# SYSMON.net
KiCad netlist of a schematic drawn in Altium Designer
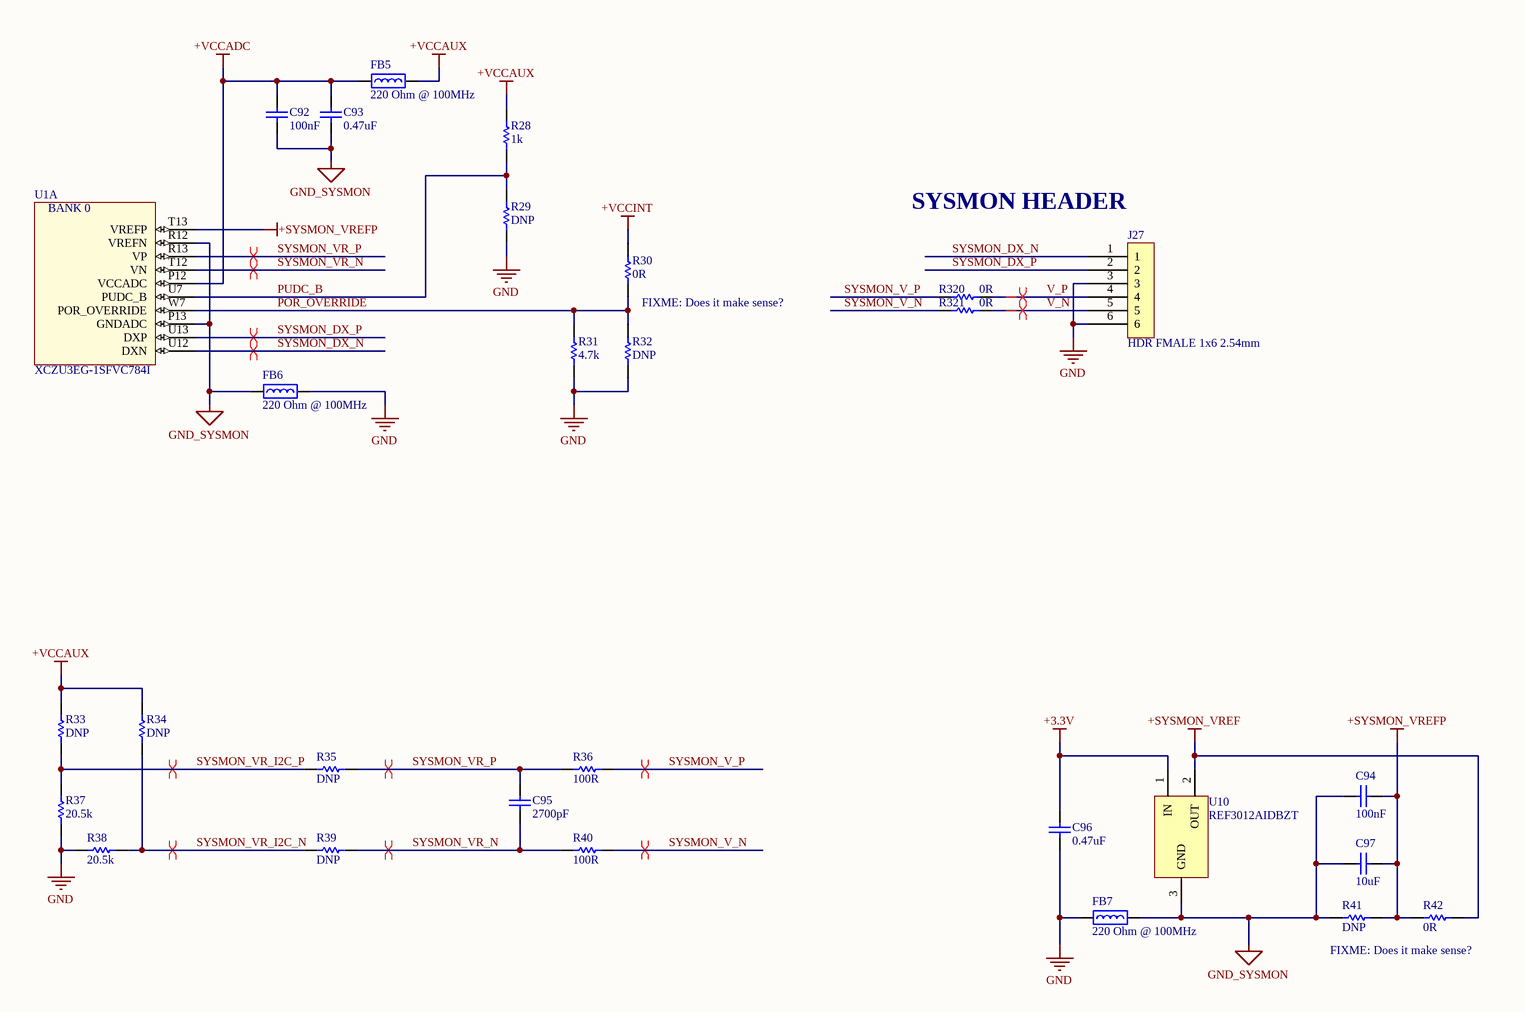
[diagram p0: SYSMON.SchDoc]

(export (version "E")
  (design (tool "Eeschema 10.0.6"))
  (components
    (comp (ref "C92")
      (value "100nF")
      (footprint "CAPC1005L_0402")
      (description "CAP CER 0.1UF 25V X7R 0402")
      (fields (field (name "VOLTAGE") "25V") (field (name "TOLERANCE") "10%"))
      (libsource (lib "Ultrascale_SchLib") (part "CAPCER0402X7R100N25V_10T"))
    )
    (comp (ref "C93")
      (value "0.47uF")
      (footprint "CAPC1005L_0402")
      (description "CAP CER 0.47UF 10V X5R 0402")
      (fields (field (name "VOLTAGE") "10V") (field (name "TOLERANCE") "10%"))
      (libsource (lib "Ultrascale_SchLib") (part "CAPCER0402X5R0U4710V_10T"))
    )
    (comp (ref "C94")
      (value "100nF")
      (footprint "CAPC1005L_0402")
      (description "CAP CER 0.1UF 25V X7R 0402")
      (fields (field (name "VOLTAGE") "25V") (field (name "TOLERANCE") "10%"))
      (libsource (lib "Ultrascale_SchLib") (part "CAPCER0402X7R100N25V_10T"))
    )
    (comp (ref "C95")
      (value "2700pF")
      (footprint "CAPC1005L_0402")
      (description "CAP CER 2700PF 50V X7R 0402")
      (fields (field (name "VOLTAGE") "50V") (field (name "TOLERANCE") "10%"))
      (libsource (lib "Ultrascale_SchLib") (part "CAPCER0402X7R2700P50V_10T"))
    )
    (comp (ref "C96")
      (value "0.47uF")
      (footprint "CAPC1005L_0402")
      (description "CAP CER 0.47UF 10V X5R 0402")
      (fields (field (name "VOLTAGE") "10V") (field (name "TOLERANCE") "10%"))
      (libsource (lib "Ultrascale_SchLib") (part "CAPCER0402X5R0U4710V_10T"))
    )
    (comp (ref "C97")
      (value "10uF")
      (footprint "CAPC1005L_0402")
      (description "CAP CER 10UF 10V X5R 0402")
      (fields (field (name "VOLTAGE") "10V") (field (name "TOLERANCE") "20%"))
      (libsource (lib "Ultrascale_SchLib") (part "CAPCER0402X5R10U10V_20T"))
    )
    (comp (ref "FB5")
      (value "BEAD0603_220_2A5_40M")
      (footprint "INDC1608N_0603")
      (description "FERRITE BEAD 220 OHM 0603 1LN")
      (fields (field (name "IMPEDANCE @ FREQUENCY") "220 Ohm @ 100MHz"))
      (libsource (lib "Ultrascale_SchLib") (part "BEAD0603_220_2A5_40M"))
    )
    (comp (ref "FB6")
      (value "BEAD0603_220_2A5_40M")
      (footprint "INDC1608N_0603")
      (description "FERRITE BEAD 220 OHM 0603 1LN")
      (fields (field (name "IMPEDANCE @ FREQUENCY") "220 Ohm @ 100MHz"))
      (libsource (lib "Ultrascale_SchLib") (part "BEAD0603_220_2A5_40M"))
    )
    (comp (ref "FB7")
      (value "BEAD0603_220_2A5_40M")
      (footprint "INDC1608N_0603")
      (description "FERRITE BEAD 220 OHM 0603 1LN")
      (fields (field (name "IMPEDANCE @ FREQUENCY") "220 Ohm @ 100MHz"))
      (libsource (lib "Ultrascale_SchLib") (part "BEAD0603_220_2A5_40M"))
    )
    (comp (ref "J27")
      (value "HDR FMALE 1x6 2.54mm")
      (footprint "Hdr_Female_1x6_2.54mm")
      (description "06-WAY SIL VERT SOCKET L/FREE")
      (fields
        (field (name ".CHECKED PCB") "MM")
        (field (name ".CHECKED SCH") "MM")
        (field (name ".CREATOR") "MM")
      )
      (libsource (lib "Ultrascale_SchLib") (part "M20-7820646"))
    )
    (comp (ref "R28")
      (value "1k")
      (footprint "RESC1005L_0402")
      (description "RES SMD 1K OHM 1% 1/10W 0402")
      (fields (field (name "POWER") "1/10W") (field (name "TOLERANCE") "1%"))
      (libsource (lib "Ultrascale_SchLib") (part "RES0402_1K_0W1_1T"))
    )
    (comp (ref "R29")
      (value "DNP")
      (footprint "RESC1005L_0402")
      (description "RES SMD 0402 Footprint")
      (fields (field (name "Comment") "RES0402"))
      (libsource (lib "Ultrascale_SchLib") (part "RES0402"))
    )
    (comp (ref "R30")
      (value "0R")
      (footprint "RESC1005L_0402")
      (description "RES SMD 0 OHM JUMPER 1/10W 0402")
      (fields (field (name "POWER") "1/10W") (field (name "Comment") "RES0402_0R_0W1"))
      (libsource (lib "Ultrascale_SchLib") (part "RES0402_0R_0W1"))
    )
    (comp (ref "R31")
      (value "4.7k")
      (footprint "RESC1005L_0402")
      (description "RES SMD 4.7K OHM 1% 1/10W 0402")
      (fields (field (name "POWER") "1/10W") (field (name "TOLERANCE") "1%"))
      (libsource (lib "Ultrascale_SchLib") (part "RES0402_4K7_0W1_1T"))
    )
    (comp (ref "R32")
      (value "DNP")
      (footprint "RESC1005L_0402")
      (description "RES SMD 0402 Footprint")
      (fields (field (name "Comment") "RES0402"))
      (libsource (lib "Ultrascale_SchLib") (part "RES0402"))
    )
    (comp (ref "R33")
      (value "DNP")
      (footprint "RESC1005L_0402")
      (description "RES SMD 0402 Footprint")
      (fields (field (name "Comment") "RES0402"))
      (libsource (lib "Ultrascale_SchLib") (part "RES0402"))
    )
    (comp (ref "R34")
      (value "DNP")
      (footprint "RESC1005L_0402")
      (description "RES SMD 0402 Footprint")
      (fields (field (name "Comment") "RES0402"))
      (libsource (lib "Ultrascale_SchLib") (part "RES0402"))
    )
    (comp (ref "R35")
      (value "DNP")
      (footprint "RESC1005L_0402")
      (description "RES SMD 0402 Footprint")
      (fields (field (name "Comment") "RES0402"))
      (libsource (lib "Ultrascale_SchLib") (part "RES0402"))
    )
    (comp (ref "R36")
      (value "100R")
      (footprint "RESC1005L_0402")
      (description "RES SMD 100 OHM 1% 1/10W 0402")
      (fields (field (name "POWER") "1/10W") (field (name "TOLERANCE") "1%"))
      (libsource (lib "Ultrascale_SchLib") (part "RES0402_100R_0W1_1T"))
    )
    (comp (ref "R37")
      (value "20.5k")
      (footprint "RESC1005L_0402")
      (description "RES SMD 20.5K OHM 1% 1/10W 0402")
      (fields (field (name "POWER") "1/10W") (field (name "TOLERANCE") "1%"))
      (libsource (lib "Ultrascale_SchLib") (part "RES0402_20K5_0W1_1T"))
    )
    (comp (ref "R38")
      (value "20.5k")
      (footprint "RESC1005L_0402")
      (description "RES SMD 20.5K OHM 1% 1/10W 0402")
      (fields (field (name "POWER") "1/10W") (field (name "TOLERANCE") "1%"))
      (libsource (lib "Ultrascale_SchLib") (part "RES0402_20K5_0W1_1T"))
    )
    (comp (ref "R39")
      (value "DNP")
      (footprint "RESC1005L_0402")
      (description "RES SMD 0402 Footprint")
      (fields (field (name "Comment") "RES0402"))
      (libsource (lib "Ultrascale_SchLib") (part "RES0402"))
    )
    (comp (ref "R40")
      (value "100R")
      (footprint "RESC1005L_0402")
      (description "RES SMD 100 OHM 1% 1/10W 0402")
      (fields (field (name "POWER") "1/10W") (field (name "TOLERANCE") "1%"))
      (libsource (lib "Ultrascale_SchLib") (part "RES0402_100R_0W1_1T"))
    )
    (comp (ref "R41")
      (value "DNP")
      (footprint "RESC1005L_0402")
      (description "RES SMD 0402 Footprint")
      (fields (field (name "Comment") "RES0402"))
      (libsource (lib "Ultrascale_SchLib") (part "RES0402"))
    )
    (comp (ref "R42")
      (value "0R")
      (footprint "RESC1005L_0402")
      (description "RES SMD 0 OHM JUMPER 1/10W 0402")
      (fields (field (name "POWER") "1/10W") (field (name "Comment") "RES0402_0R_0W1"))
      (libsource (lib "Ultrascale_SchLib") (part "RES0402_0R_0W1"))
    )
    (comp (ref "R320")
      (value "0R")
      (footprint "RESC1005L_0402")
      (description "RES SMD 0 OHM JUMPER 1/10W 0402")
      (fields (field (name "POWER") "1/10W") (field (name "Comment") "RES0402_0R_0W1"))
      (libsource (lib "Ultrascale_SchLib") (part "RES0402_0R_0W1"))
    )
    (comp (ref "R321")
      (value "0R")
      (footprint "RESC1005L_0402")
      (description "RES SMD 0 OHM JUMPER 1/10W 0402")
      (fields (field (name "POWER") "1/10W") (field (name "Comment") "RES0402_0R_0W1"))
      (libsource (lib "Ultrascale_SchLib") (part "RES0402_0R_0W1"))
    )
    (comp (ref "U1")
      (value "XCZU3EG-1SFVC784I")
      (footprint "BGA784x28")
      (description "IC FPGA 252 I/O 784FCBGA - XILINX ZYNQ ULTRASCALE+")
      (libsource (lib "Ultrascale_SchLib") (part "XCZU3EG-1SFVC784I"))
    )
    (comp (ref "U10")
      (value "REF3012AIDBZT")
      (footprint "TI-DBZ3_N")
      (description "IC VREF SERIES 1.25V SOT23-3")
      (libsource (lib "Ultrascale_SchLib") (part "REF3012AIDBZT"))
    )
  )
  (nets
    (net (code "1") (name "+3.3V") (class "Default")
      (node (ref "C96") (pin "1") (pinfunction "1_1") (pintype "passive"))
      (node (ref "U10") (pin "1") (pinfunction "IN_1") (pintype "passive"))
    )
    (net (code "2") (name "+SYSMON_VREF") (class "Default")
      (node (ref "R42") (pin "1") (pinfunction "1_1") (pintype "passive"))
      (node (ref "U10") (pin "2") (pinfunction "OUT_2") (pintype "passive"))
    )
    (net (code "3") (name "+SYSMON_VREFP") (class "Default")
      (node (ref "C94") (pin "1") (pinfunction "1_1") (pintype "passive"))
      (node (ref "C97") (pin "2") (pinfunction "2_2") (pintype "passive"))
      (node (ref "R41") (pin "1") (pinfunction "1_1") (pintype "passive"))
      (node (ref "R42") (pin "2") (pinfunction "2_2") (pintype "passive"))
      (node (ref "U1") (pin "T13") (pinfunction "VREFP_T13") (pintype "bidirectional"))
    )
    (net (code "4") (name "+VCCADC") (class "Default")
      (node (ref "C92") (pin "1") (pinfunction "1_1") (pintype "passive"))
      (node (ref "C93") (pin "1") (pinfunction "1_1") (pintype "passive"))
      (node (ref "FB5") (pin "1") (pinfunction "1_1") (pintype "passive"))
      (node (ref "U1") (pin "P12") (pinfunction "VCCADC_P12") (pintype "bidirectional"))
    )
    (net (code "5") (name "+VCCAUX") (class "Default")
      (node (ref "FB5") (pin "2") (pinfunction "2_2") (pintype "passive"))
      (node (ref "R28") (pin "1") (pinfunction "1_1") (pintype "passive"))
      (node (ref "R33") (pin "1") (pinfunction "1_1") (pintype "passive"))
      (node (ref "R34") (pin "1") (pinfunction "1_1") (pintype "passive"))
    )
    (net (code "6") (name "+VCCINT") (class "Default")
      (node (ref "R30") (pin "1") (pinfunction "1_1") (pintype "passive"))
    )
    (net (code "7") (name "/POR_OVERRIDE") (class "Default")
      (node (ref "R30") (pin "2") (pinfunction "2_2") (pintype "passive"))
      (node (ref "R31") (pin "1") (pinfunction "1_1") (pintype "passive"))
      (node (ref "R32") (pin "1") (pinfunction "1_1") (pintype "passive"))
      (node (ref "U1") (pin "W7") (pinfunction "POR_OVERRIDE_W7") (pintype "bidirectional"))
    )
    (net (code "8") (name "/PUDC_B") (class "Default")
      (node (ref "R28") (pin "2") (pinfunction "2_2") (pintype "passive"))
      (node (ref "R29") (pin "1") (pinfunction "1_1") (pintype "passive"))
      (node (ref "U1") (pin "U7") (pinfunction "PUDC_B_U7") (pintype "bidirectional"))
    )
    (net (code "9") (name "/SYSMON_DX_N") (class "Default")
      (node (ref "J27") (pin "1") (pinfunction "1_1") (pintype "passive"))
      (node (ref "U1") (pin "U12") (pinfunction "DXN_U12") (pintype "bidirectional"))
    )
    (net (code "10") (name "/SYSMON_DX_P") (class "Default")
      (node (ref "J27") (pin "2") (pinfunction "2_2") (pintype "passive"))
      (node (ref "U1") (pin "U13") (pinfunction "DXP_U13") (pintype "bidirectional"))
    )
    (net (code "11") (name "/SYSMON_VR_I2C_N") (class "Default")
      (node (ref "R34") (pin "2") (pinfunction "2_2") (pintype "passive"))
      (node (ref "R38") (pin "1") (pinfunction "1_1") (pintype "passive"))
      (node (ref "R39") (pin "2") (pinfunction "2_2") (pintype "passive"))
    )
    (net (code "12") (name "/SYSMON_VR_I2C_P") (class "Default")
      (node (ref "R33") (pin "2") (pinfunction "2_2") (pintype "passive"))
      (node (ref "R35") (pin "2") (pinfunction "2_2") (pintype "passive"))
      (node (ref "R37") (pin "1") (pinfunction "1_1") (pintype "passive"))
    )
    (net (code "13") (name "/SYSMON_VR_N") (class "Default")
      (node (ref "C95") (pin "2") (pinfunction "2_2") (pintype "passive"))
      (node (ref "R39") (pin "1") (pinfunction "1_1") (pintype "passive"))
      (node (ref "R40") (pin "1") (pinfunction "1_1") (pintype "passive"))
      (node (ref "U1") (pin "T12") (pinfunction "VN_T12") (pintype "bidirectional"))
    )
    (net (code "14") (name "/SYSMON_VR_P") (class "Default")
      (node (ref "C95") (pin "1") (pinfunction "1_1") (pintype "passive"))
      (node (ref "R35") (pin "1") (pinfunction "1_1") (pintype "passive"))
      (node (ref "R36") (pin "1") (pinfunction "1_1") (pintype "passive"))
      (node (ref "U1") (pin "R13") (pinfunction "VP_R13") (pintype "bidirectional"))
    )
    (net (code "15") (name "/SYSMON_V_N") (class "Default")
      (node (ref "R321") (pin "1") (pinfunction "1_1") (pintype "passive"))
      (node (ref "R40") (pin "2") (pinfunction "2_2") (pintype "passive"))
    )
    (net (code "16") (name "/SYSMON_V_P") (class "Default")
      (node (ref "R320") (pin "1") (pinfunction "1_1") (pintype "passive"))
      (node (ref "R36") (pin "2") (pinfunction "2_2") (pintype "passive"))
    )
    (net (code "17") (name "/V_N") (class "Default")
      (node (ref "J27") (pin "5") (pinfunction "5_5") (pintype "passive"))
      (node (ref "R321") (pin "2") (pinfunction "2_2") (pintype "passive"))
    )
    (net (code "18") (name "/V_P") (class "Default")
      (node (ref "J27") (pin "4") (pinfunction "4_4") (pintype "passive"))
      (node (ref "R320") (pin "2") (pinfunction "2_2") (pintype "passive"))
    )
    (net (code "19") (name "GND") (class "Default")
      (node (ref "C96") (pin "2") (pinfunction "2_2") (pintype "passive"))
      (node (ref "FB6") (pin "2") (pinfunction "2_2") (pintype "passive"))
      (node (ref "FB7") (pin "1") (pinfunction "1_1") (pintype "passive"))
      (node (ref "J27") (pin "3") (pinfunction "3_3") (pintype "passive"))
      (node (ref "J27") (pin "6") (pinfunction "6_6") (pintype "passive"))
      (node (ref "R29") (pin "2") (pinfunction "2_2") (pintype "passive"))
      (node (ref "R31") (pin "2") (pinfunction "2_2") (pintype "passive"))
      (node (ref "R32") (pin "2") (pinfunction "2_2") (pintype "passive"))
      (node (ref "R37") (pin "2") (pinfunction "2_2") (pintype "passive"))
      (node (ref "R38") (pin "2") (pinfunction "2_2") (pintype "passive"))
    )
    (net (code "20") (name "GND_SYSMON") (class "Default")
      (node (ref "C92") (pin "2") (pinfunction "2_2") (pintype "passive"))
      (node (ref "C93") (pin "2") (pinfunction "2_2") (pintype "passive"))
      (node (ref "C94") (pin "2") (pinfunction "2_2") (pintype "passive"))
      (node (ref "C97") (pin "1") (pinfunction "1_1") (pintype "passive"))
      (node (ref "FB6") (pin "1") (pinfunction "1_1") (pintype "passive"))
      (node (ref "FB7") (pin "2") (pinfunction "2_2") (pintype "passive"))
      (node (ref "R41") (pin "2") (pinfunction "2_2") (pintype "passive"))
      (node (ref "U1") (pin "P13") (pinfunction "GNDADC_P13") (pintype "bidirectional"))
      (node (ref "U1") (pin "R12") (pinfunction "VREFN_R12") (pintype "bidirectional"))
      (node (ref "U10") (pin "3") (pinfunction "GND_3") (pintype "passive"))
    )
  )
)
